# WT2_Power.net
KiCad netlist of a schematic drawn in Altium Designer
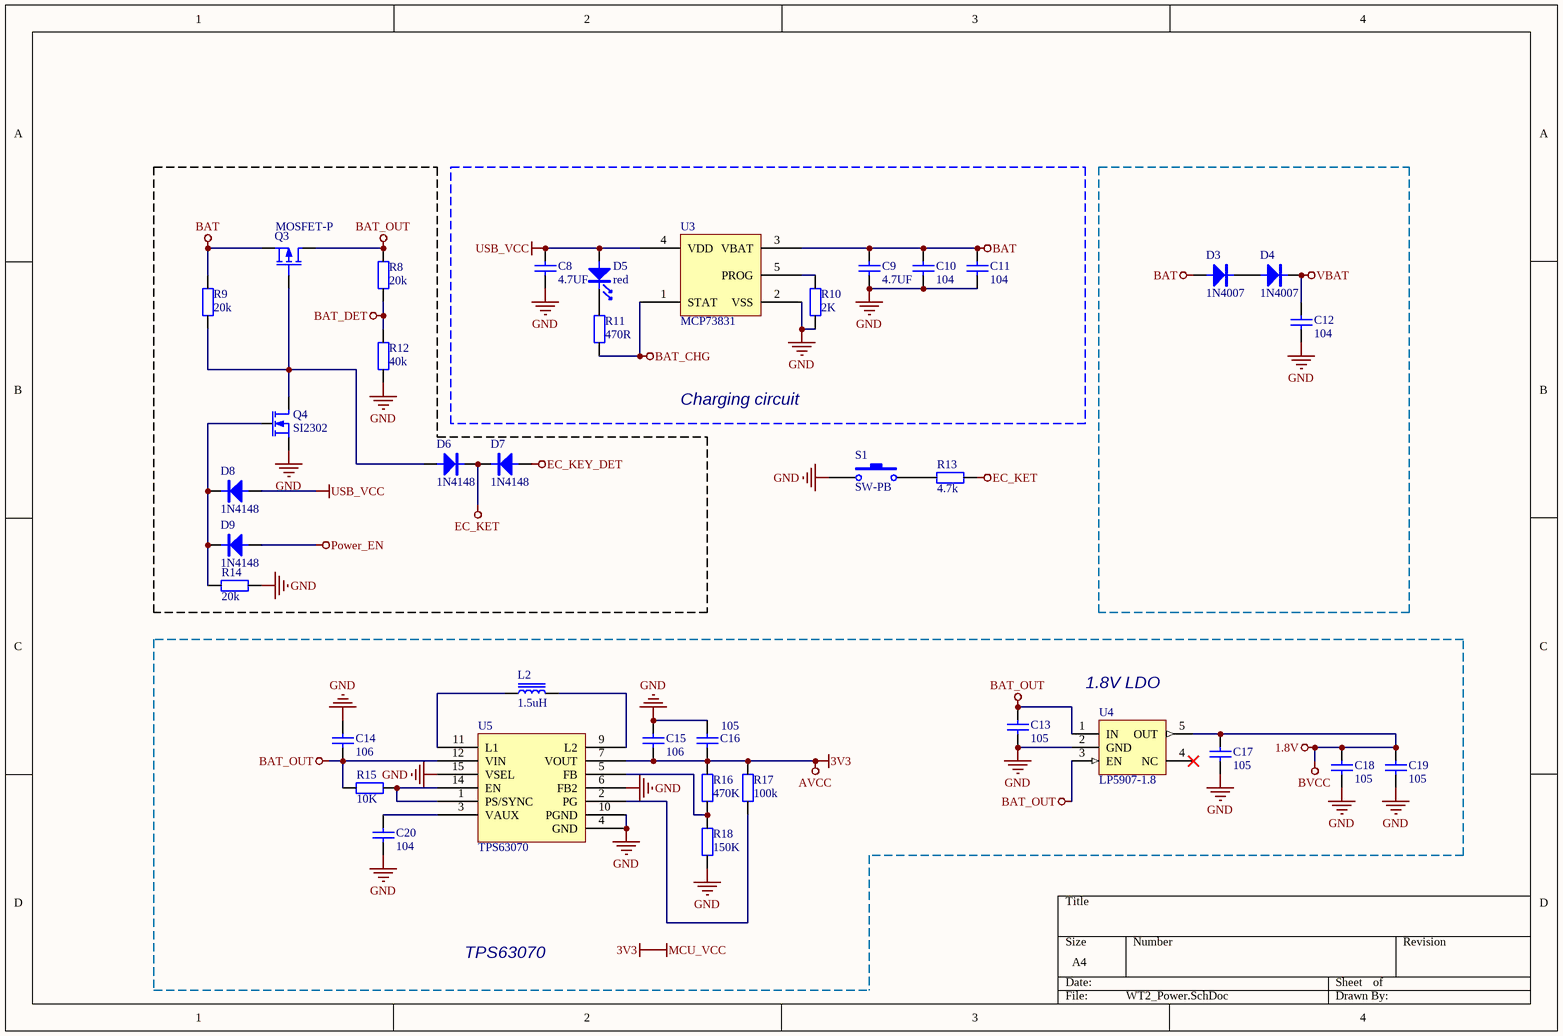
[diagram p0: WT2_Power.SchDoc]

(export (version "E")
  (design (tool "Eeschema 10.0.6"))
  (components
    (comp (ref "C8")
      (value "4.7UF")
      (footprint "电容_C0805")
      (fields (field (name "C") "4.7UF"))
      (libsource (lib "元件库") (part "cap"))
    )
    (comp (ref "C9")
      (value "4.7UF")
      (footprint "电容_C0805")
      (fields (field (name "C") "4.7UF"))
      (libsource (lib "元件库") (part "cap"))
    )
    (comp (ref "C10")
      (value "104")
      (footprint "电容_C0402")
      (fields (field (name "C") "104"))
      (libsource (lib "元件库") (part "cap"))
    )
    (comp (ref "C11")
      (value "104")
      (footprint "电容_C0402")
      (fields (field (name "C") "104"))
      (libsource (lib "元件库") (part "cap"))
    )
    (comp (ref "C12")
      (value "104")
      (footprint "电容_C0402")
      (fields (field (name "C") "104"))
      (libsource (lib "元件库") (part "cap"))
    )
    (comp (ref "C13")
      (value "105")
      (footprint "电容_C0402")
      (fields (field (name "C") "105"))
      (libsource (lib "元件库") (part "cap"))
    )
    (comp (ref "C14")
      (value "106")
      (footprint "电容_C0805")
      (fields (field (name "C") "106"))
      (libsource (lib "元件库") (part "cap"))
    )
    (comp (ref "C15")
      (value "106")
      (footprint "电容_C0603")
      (fields (field (name "C") "106"))
      (libsource (lib "元件库") (part "cap"))
    )
    (comp (ref "C16")
      (value "105")
      (footprint "电容_C0402")
      (fields (field (name "C") "105"))
      (libsource (lib "元件库") (part "cap"))
    )
    (comp (ref "C17")
      (value "105")
      (footprint "电容_C0402")
      (fields (field (name "C") "105"))
      (libsource (lib "元件库") (part "cap"))
    )
    (comp (ref "C18")
      (value "105")
      (footprint "电容_C0402")
      (fields (field (name "C") "105"))
      (libsource (lib "元件库") (part "cap"))
    )
    (comp (ref "C19")
      (value "105")
      (footprint "电容_C0402")
      (fields (field (name "C") "105"))
      (libsource (lib "元件库") (part "cap"))
    )
    (comp (ref "C20")
      (value "104")
      (footprint "电容_C0402")
      (fields (field (name "C") "104"))
      (libsource (lib "元件库") (part "cap"))
    )
    (comp (ref "D3")
      (value "1N4007")
      (footprint "二极管_SOD-323")
      (fields (field (name "_MODEL") "1N4007"))
      (libsource (lib "元件库") (part "Diode"))
    )
    (comp (ref "D4")
      (value "1N4007")
      (footprint "二极管_SOD-323")
      (fields (field (name "_MODEL") "1N4007"))
      (libsource (lib "元件库") (part "Diode"))
    )
    (comp (ref "D5") (value "red") (footprint "LED_0603") (libsource (lib "元件库") (part "LED")))
    (comp (ref "D6")
      (value "1N4148")
      (footprint "二极管_SOD-323")
      (fields (field (name "_MODEL") "1N4148"))
      (libsource (lib "元件库") (part "Diode"))
    )
    (comp (ref "D7")
      (value "1N4148")
      (footprint "二极管_SOD-323")
      (fields (field (name "_MODEL") "1N4148"))
      (libsource (lib "元件库") (part "Diode"))
    )
    (comp (ref "D8")
      (value "1N4148")
      (footprint "二极管_SOD-323")
      (fields (field (name "_MODEL") "1N4148"))
      (libsource (lib "元件库") (part "Diode"))
    )
    (comp (ref "D9")
      (value "1N4148")
      (footprint "二极管_SOD-323")
      (fields (field (name "_MODEL") "1N4148"))
      (libsource (lib "元件库") (part "Diode"))
    )
    (comp (ref "L2")
      (value "1.5uH")
      (footprint "变压器电感_0420")
      (fields (field (name "_VALUE") "1.5uH"))
      (libsource (lib "元件库") (part "Inductor Iron 2"))
    )
    (comp (ref "Q3")
      (value "MOSFET-P")
      (footprint "SOT23")
      (description "P-Channel MOSFET")
      (fields (field (name "PUBLISHER") "Altium Limited"))
      (libsource (lib "我的元件库") (part "MOSFET-P"))
    )
    (comp (ref "Q4")
      (value "SI2302")
      (footprint "MOS_SOT-23")
      (fields (field (name "_MODEL") "SI2302"))
      (libsource (lib "元件库") (part "MOSFET-N"))
    )
    (comp (ref "R8")
      (value "20k")
      (footprint "电阻_R0402")
      (fields (field (name "R") "20k"))
      (libsource (lib "") (part "Res_2"))
    )
    (comp (ref "R9")
      (value "20k")
      (footprint "电阻_R0402")
      (fields (field (name "R") "20k"))
      (libsource (lib "") (part "Res_2"))
    )
    (comp (ref "R10")
      (value "2K")
      (footprint "电阻_R0402")
      (fields (field (name "R") "2K"))
      (libsource (lib "") (part "Res_2"))
    )
    (comp (ref "R11")
      (value "470R")
      (footprint "电阻_R0402")
      (fields (field (name "R") "470R"))
      (libsource (lib "") (part "Res_2"))
    )
    (comp (ref "R12")
      (value "40k")
      (footprint "电阻_R0402")
      (fields (field (name "R") "40k"))
      (libsource (lib "") (part "Res_2"))
    )
    (comp (ref "R13")
      (value "4.7k")
      (footprint "电阻_R0402")
      (fields (field (name "R") "4.7k"))
      (libsource (lib "元件库") (part "Res"))
    )
    (comp (ref "R14")
      (value "20k")
      (footprint "电阻_R0402")
      (fields (field (name "R") "20k"))
      (libsource (lib "元件库") (part "Res"))
    )
    (comp (ref "R15")
      (value "10K")
      (footprint "电阻_R0402")
      (fields (field (name "R") "10K"))
      (libsource (lib "元件库") (part "Res"))
    )
    (comp (ref "R16")
      (value "470K")
      (footprint "电阻_R0402")
      (fields (field (name "R") "470K"))
      (libsource (lib "") (part "Res_1"))
    )
    (comp (ref "R17")
      (value "100k")
      (footprint "电阻_R0402")
      (fields (field (name "R") "100k"))
      (libsource (lib "") (part "Res_1"))
    )
    (comp (ref "R18")
      (value "150K")
      (footprint "电阻_R0402")
      (fields (field (name "R") "150K"))
      (libsource (lib "") (part "Res_1"))
    )
    (comp (ref "S1")
      (value "SW-PB")
      (footprint "TriggersLib:KEY-TE26EA")
      (description "按键")
      (libsource (lib "TriggersLib") (part "SW-PB"))
    )
    (comp (ref "U3")
      (value "MCP73831")
      (footprint "TriggersLib:SOT23-5")
      (description "线性充电管理控制器")
      (libsource (lib "TriggersLib") (part "MCP73831"))
    )
    (comp (ref "U4")
      (value "LP5907-1.8")
      (footprint "SOT23-5")
      (description "LDO")
      (libsource (lib "WatchX_TEST") (part "LP5907"))
    )
    (comp (ref "U5")
      (value "TPS63070")
      (footprint "VQFN-15-HR")
      (description "降压-升压转换器")
      (libsource (lib "TriggersLib") (part "TPS63070"))
    )
  )
  (nets
    (net (code "1") (name "1.8V") (class "Default")
      (node (ref "C17") (pin "2") (pinfunction "2_2") (pintype "passive"))
      (node (ref "C18") (pin "2") (pinfunction "2_2") (pintype "passive"))
      (node (ref "C19") (pin "2") (pinfunction "2_2") (pintype "passive"))
      (node (ref "U4") (pin "5") (pinfunction "OUT_5") (pintype "output"))
    )
    (net (code "2") (name "3V3") (class "Default")
      (node (ref "C15") (pin "1") (pinfunction "1_1") (pintype "passive"))
      (node (ref "C16") (pin "1") (pinfunction "1_1") (pintype "passive"))
      (node (ref "R16") (pin "1") (pinfunction "1_1") (pintype "passive"))
      (node (ref "R17") (pin "1") (pinfunction "1_1") (pintype "passive"))
      (node (ref "U5") (pin "7") (pinfunction "VOUT_7") (pintype "passive"))
    )
    (net (code "3") (name "BAT") (class "Default")
      (node (ref "C10") (pin "1") (pinfunction "1_1") (pintype "passive"))
      (node (ref "C11") (pin "1") (pinfunction "1_1") (pintype "passive"))
      (node (ref "C9") (pin "2") (pinfunction "2_2") (pintype "passive"))
      (node (ref "D3") (pin "A") (pinfunction "A_A") (pintype "passive"))
      (node (ref "Q3") (pin "3") (pinfunction "S_3") (pintype "passive"))
      (node (ref "R9") (pin "2") (pinfunction "2_2") (pintype "passive"))
      (node (ref "U3") (pin "3") (pinfunction "VBAT_3") (pintype "passive"))
    )
    (net (code "4") (name "BAT_CHG") (class "Default")
      (node (ref "R11") (pin "1") (pinfunction "1_1") (pintype "passive"))
      (node (ref "U3") (pin "1") (pinfunction "STAT_1") (pintype "passive"))
    )
    (net (code "5") (name "BAT_DET") (class "Default")
      (node (ref "R12") (pin "2") (pinfunction "2_2") (pintype "passive"))
      (node (ref "R8") (pin "1") (pinfunction "1_1") (pintype "passive"))
    )
    (net (code "6") (name "BAT_OUT") (class "Default")
      (node (ref "C13") (pin "2") (pinfunction "2_2") (pintype "passive"))
      (node (ref "C14") (pin "1") (pinfunction "1_1") (pintype "passive"))
      (node (ref "Q3") (pin "2") (pinfunction "D_2") (pintype "passive"))
      (node (ref "R15") (pin "2") (pinfunction "2_2") (pintype "passive"))
      (node (ref "R8") (pin "2") (pinfunction "2_2") (pintype "passive"))
      (node (ref "U4") (pin "1") (pinfunction "IN_1") (pintype "power_in"))
      (node (ref "U4") (pin "3") (pinfunction "EN_3") (pintype "input"))
      (node (ref "U5") (pin "12") (pinfunction "VIN_12") (pintype "passive"))
    )
    (net (code "7") (name "EC_KET") (class "Default")
      (node (ref "D6") (pin "K") (pinfunction "K_K") (pintype "passive"))
      (node (ref "D7") (pin "K") (pinfunction "K_K") (pintype "passive"))
      (node (ref "R13") (pin "1") (pinfunction "1_1") (pintype "passive"))
    )
    (net (code "8") (name "EC_KEY_DET") (class "Default")
      (node (ref "D7") (pin "A") (pinfunction "A_A") (pintype "passive"))
    )
    (net (code "9") (name "GND") (class "Default")
      (node (ref "C10") (pin "2") (pinfunction "2_2") (pintype "passive"))
      (node (ref "C11") (pin "2") (pinfunction "2_2") (pintype "passive"))
      (node (ref "C12") (pin "2") (pinfunction "2_2") (pintype "passive"))
      (node (ref "C13") (pin "1") (pinfunction "1_1") (pintype "passive"))
      (node (ref "C14") (pin "2") (pinfunction "2_2") (pintype "passive"))
      (node (ref "C15") (pin "2") (pinfunction "2_2") (pintype "passive"))
      (node (ref "C16") (pin "2") (pinfunction "2_2") (pintype "passive"))
      (node (ref "C17") (pin "1") (pinfunction "1_1") (pintype "passive"))
      (node (ref "C18") (pin "1") (pinfunction "1_1") (pintype "passive"))
      (node (ref "C19") (pin "1") (pinfunction "1_1") (pintype "passive"))
      (node (ref "C20") (pin "1") (pinfunction "1_1") (pintype "passive"))
      (node (ref "C8") (pin "1") (pinfunction "1_1") (pintype "passive"))
      (node (ref "C9") (pin "1") (pinfunction "1_1") (pintype "passive"))
      (node (ref "Q4") (pin "3") (pinfunction "S_3") (pintype "passive"))
      (node (ref "R10") (pin "1") (pinfunction "1_1") (pintype "passive"))
      (node (ref "R12") (pin "1") (pinfunction "1_1") (pintype "passive"))
      (node (ref "R14") (pin "1") (pinfunction "1_1") (pintype "passive"))
      (node (ref "R18") (pin "2") (pinfunction "2_2") (pintype "passive"))
      (node (ref "S1") (pin "1") (pinfunction "1_1") (pintype "passive"))
      (node (ref "U3") (pin "2") (pinfunction "VSS_2") (pintype "passive"))
      (node (ref "U4") (pin "2") (pinfunction "GND_2") (pintype "passive"))
      (node (ref "U5") (pin "10") (pinfunction "PGND_10") (pintype "passive"))
      (node (ref "U5") (pin "15") (pinfunction "VSEL_15") (pintype "passive"))
      (node (ref "U5") (pin "4") (pinfunction "GND_4") (pintype "passive"))
      (node (ref "U5") (pin "6") (pinfunction "FB2_6") (pintype "passive"))
    )
    (net (code "10") (name "Net-(D3-PadK)") (class "Default")
      (node (ref "D3") (pin "K") (pinfunction "K_K") (pintype "passive"))
      (node (ref "D4") (pin "A") (pinfunction "A_A") (pintype "passive"))
    )
    (net (code "11") (name "Net-(D5-PadK)") (class "Default")
      (node (ref "D5") (pin "K") (pinfunction "K_K") (pintype "passive"))
      (node (ref "R11") (pin "2") (pinfunction "2_2") (pintype "passive"))
    )
    (net (code "12") (name "Net-(Q3-G)") (class "Default")
      (node (ref "D6") (pin "A") (pinfunction "A_A") (pintype "passive"))
      (node (ref "Q3") (pin "1") (pinfunction "G_1") (pintype "passive"))
      (node (ref "Q4") (pin "2") (pinfunction "D_2") (pintype "passive"))
      (node (ref "R9") (pin "1") (pinfunction "1_1") (pintype "passive"))
    )
    (net (code "13") (name "Net-(Q4-G)") (class "Default")
      (node (ref "D8") (pin "K") (pinfunction "K_K") (pintype "passive"))
      (node (ref "D9") (pin "K") (pinfunction "K_K") (pintype "passive"))
      (node (ref "Q4") (pin "1") (pinfunction "G_1") (pintype "passive"))
      (node (ref "R14") (pin "2") (pinfunction "2_2") (pintype "passive"))
    )
    (net (code "14") (name "Net-(R13-Pad2)") (class "Default")
      (node (ref "R13") (pin "2") (pinfunction "2_2") (pintype "passive"))
      (node (ref "S1") (pin "2") (pinfunction "2_2") (pintype "passive"))
    )
    (net (code "15") (name "Net-(U3-PROG)") (class "Default")
      (node (ref "R10") (pin "2") (pinfunction "2_2") (pintype "passive"))
      (node (ref "U3") (pin "5") (pinfunction "PROG_5") (pintype "passive"))
    )
    (net (code "16") (name "Net-(U5-EN)") (class "Default")
      (node (ref "R15") (pin "1") (pinfunction "1_1") (pintype "passive"))
      (node (ref "U5") (pin "1") (pinfunction "PS/SYNC_1") (pintype "passive"))
      (node (ref "U5") (pin "14") (pinfunction "EN_14") (pintype "passive"))
    )
    (net (code "17") (name "Net-(U5-FB)") (class "Default")
      (node (ref "R16") (pin "2") (pinfunction "2_2") (pintype "passive"))
      (node (ref "R18") (pin "1") (pinfunction "1_1") (pintype "passive"))
      (node (ref "U5") (pin "5") (pinfunction "FB_5") (pintype "passive"))
    )
    (net (code "18") (name "Net-(U5-L1)") (class "Default")
      (node (ref "L2") (pin "1") (pinfunction "1_1") (pintype "passive"))
      (node (ref "U5") (pin "11") (pinfunction "L1_11") (pintype "passive"))
    )
    (net (code "19") (name "Net-(U5-L2)") (class "Default")
      (node (ref "L2") (pin "2") (pinfunction "2_2") (pintype "passive"))
      (node (ref "U5") (pin "9") (pinfunction "L2_9") (pintype "passive"))
    )
    (net (code "20") (name "Net-(U5-PG)") (class "Default")
      (node (ref "R17") (pin "2") (pinfunction "2_2") (pintype "passive"))
      (node (ref "U5") (pin "2") (pinfunction "PG_2") (pintype "passive"))
    )
    (net (code "21") (name "Net-(U5-VAUX)") (class "Default")
      (node (ref "C20") (pin "2") (pinfunction "2_2") (pintype "passive"))
      (node (ref "U5") (pin "3") (pinfunction "VAUX_3") (pintype "passive"))
    )
    (net (code "22") (name "Power_EN") (class "Default")
      (node (ref "D9") (pin "A") (pinfunction "A_A") (pintype "passive"))
    )
    (net (code "23") (name "USB_VCC") (class "Default")
      (node (ref "C8") (pin "2") (pinfunction "2_2") (pintype "passive"))
      (node (ref "D5") (pin "A") (pinfunction "A_A") (pintype "passive"))
      (node (ref "D8") (pin "A") (pinfunction "A_A") (pintype "passive"))
      (node (ref "U3") (pin "4") (pinfunction "VDD_4") (pintype "passive"))
    )
    (net (code "24") (name "VBAT") (class "Default")
      (node (ref "C12") (pin "1") (pinfunction "1_1") (pintype "passive"))
      (node (ref "D4") (pin "K") (pinfunction "K_K") (pintype "passive"))
    )
    (net (code "25") (name "unconnected-(U4-NC-Pad4)") (class "Default")
      (node (ref "U4") (pin "4") (pinfunction "NC_4") (pintype "passive+no_connect"))
    )
  )
)
